# P01_Power_Management.net
KiCad netlist of a schematic drawn in Altium Designer
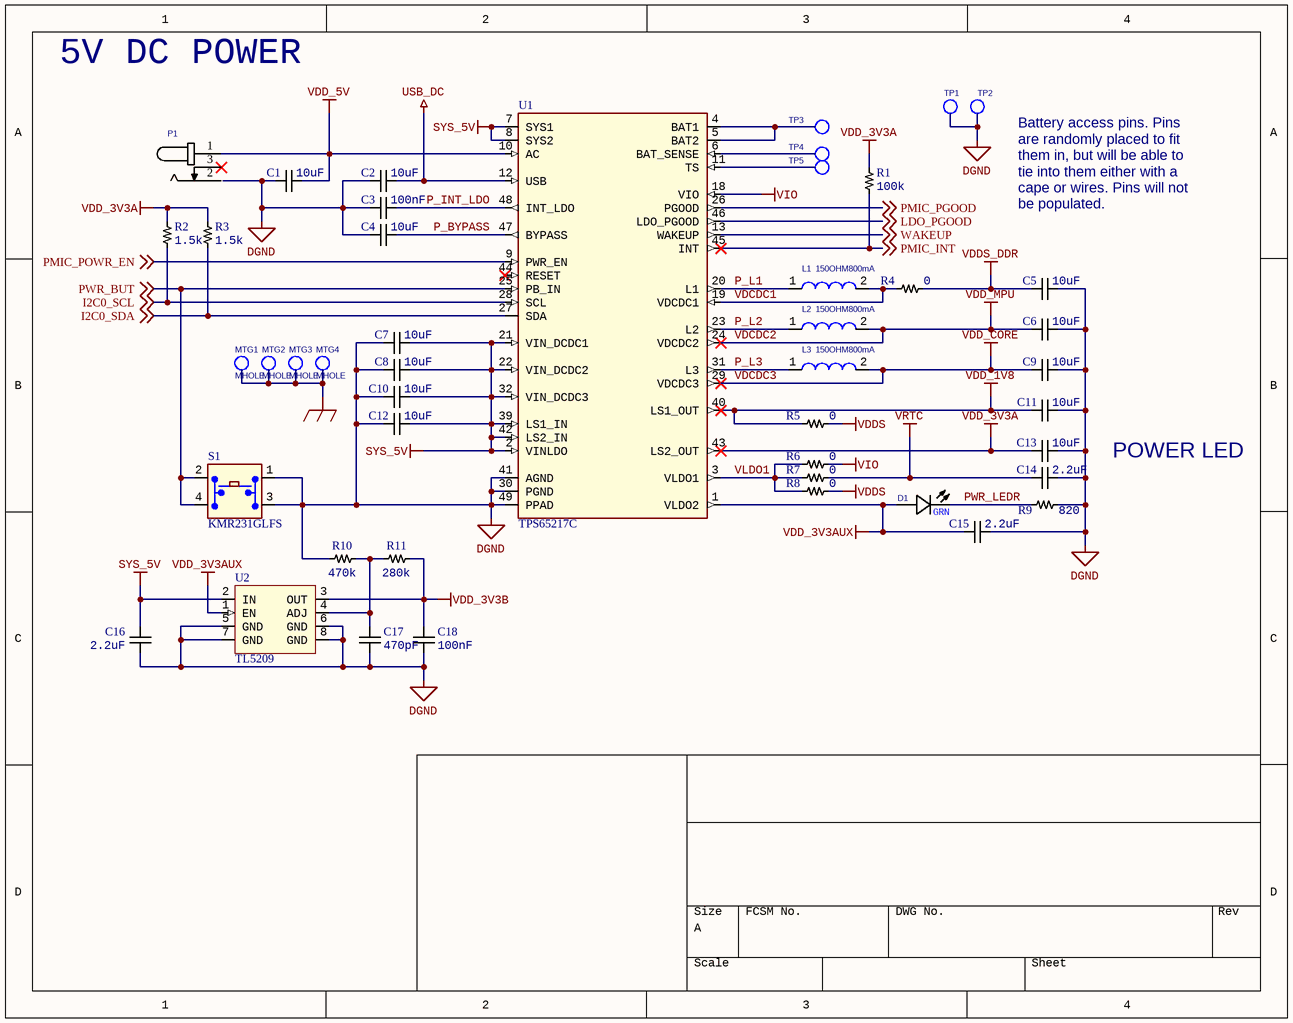
[diagram p0: P01_Power Management.SchDoc]

(export (version "E")
  (design (tool "Eeschema 10.0.6"))
  (components
    (comp (ref "C1")
      (value "C2012X6S1A106K085AC")
      (footprint "CAP0805")
      (description "MLCC 10uF 0805 SMD")
      (fields
        (field (name "MANUFACTURER") "TDK")
        (field (name "TOLERANCE") "10%")
        (field (name "CAPACITANCE") "10uF")
      )
      (libsource (lib "Orient2") (part "CAP_10uF"))
    )
    (comp (ref "C2")
      (value "C2012X6S1A106K085AC")
      (footprint "CAP0805")
      (description "MLCC 10uF 0805 SMD")
      (fields
        (field (name "MANUFACTURER") "TDK")
        (field (name "TOLERANCE") "10%")
        (field (name "CAPACITANCE") "10uF")
      )
      (libsource (lib "Orient2") (part "CAP_10uF"))
    )
    (comp (ref "C3")
      (value "C0402C104K4RACTU")
      (footprint "CAP0402")
      (description "MLCC 100nF 0402 SMD")
      (fields
        (field (name "MANUFACTURER") "KEMET")
        (field (name "TOLERANCE") "10%")
        (field (name "CAPACITANCE") "100nF")
      )
      (libsource (lib "Orient2") (part "CAP_100nF"))
    )
    (comp (ref "C4")
      (value "C2012X6S1A106K085AC")
      (footprint "CAP0805")
      (description "MLCC 10uF 0805 SMD")
      (fields
        (field (name "MANUFACTURER") "TDK")
        (field (name "TOLERANCE") "10%")
        (field (name "CAPACITANCE") "10uF")
      )
      (libsource (lib "Orient2") (part "CAP_10uF"))
    )
    (comp (ref "C5")
      (value "C2012X6S1A106K085AC")
      (footprint "CAP0805")
      (description "MLCC 10uF 0805 SMD")
      (fields
        (field (name "MANUFACTURER") "TDK")
        (field (name "TOLERANCE") "10%")
        (field (name "CAPACITANCE") "10uF")
      )
      (libsource (lib "Orient2") (part "CAP_10uF"))
    )
    (comp (ref "C6")
      (value "C2012X6S1A106K085AC")
      (footprint "CAP0805")
      (description "MLCC 10uF 0805 SMD")
      (fields
        (field (name "MANUFACTURER") "TDK")
        (field (name "TOLERANCE") "10%")
        (field (name "CAPACITANCE") "10uF")
      )
      (libsource (lib "Orient2") (part "CAP_10uF"))
    )
    (comp (ref "C7")
      (value "C2012X6S1A106K085AC")
      (footprint "CAP0805")
      (description "MLCC 10uF 0805 SMD")
      (fields
        (field (name "MANUFACTURER") "TDK")
        (field (name "TOLERANCE") "10%")
        (field (name "CAPACITANCE") "10uF")
      )
      (libsource (lib "Orient2") (part "CAP_10uF"))
    )
    (comp (ref "C8")
      (value "C2012X6S1A106K085AC")
      (footprint "CAP0805")
      (description "MLCC 10uF 0805 SMD")
      (fields
        (field (name "MANUFACTURER") "TDK")
        (field (name "TOLERANCE") "10%")
        (field (name "CAPACITANCE") "10uF")
      )
      (libsource (lib "Orient2") (part "CAP_10uF"))
    )
    (comp (ref "C9")
      (value "C2012X6S1A106K085AC")
      (footprint "CAP0805")
      (description "MLCC 10uF 0805 SMD")
      (fields
        (field (name "MANUFACTURER") "TDK")
        (field (name "TOLERANCE") "10%")
        (field (name "CAPACITANCE") "10uF")
      )
      (libsource (lib "Orient2") (part "CAP_10uF"))
    )
    (comp (ref "C10")
      (value "C2012X6S1A106K085AC")
      (footprint "CAP0805")
      (description "MLCC 10uF 0805 SMD")
      (fields
        (field (name "MANUFACTURER") "TDK")
        (field (name "TOLERANCE") "10%")
        (field (name "CAPACITANCE") "10uF")
      )
      (libsource (lib "Orient2") (part "CAP_10uF"))
    )
    (comp (ref "C11")
      (value "C2012X6S1A106K085AC")
      (footprint "CAP0805")
      (description "MLCC 10uF 0805 SMD")
      (fields
        (field (name "MANUFACTURER") "TDK")
        (field (name "TOLERANCE") "10%")
        (field (name "CAPACITANCE") "10uF")
      )
      (libsource (lib "Orient2") (part "CAP_10uF"))
    )
    (comp (ref "C12")
      (value "C2012X6S1A106K085AC")
      (footprint "CAP0805")
      (description "MLCC 10uF 0805 SMD")
      (fields
        (field (name "MANUFACTURER") "TDK")
        (field (name "TOLERANCE") "10%")
        (field (name "CAPACITANCE") "10uF")
      )
      (libsource (lib "Orient2") (part "CAP_10uF"))
    )
    (comp (ref "C13")
      (value "C2012X6S1A106K085AC")
      (footprint "CAP0805")
      (description "MLCC 10uF 0805 SMD")
      (fields
        (field (name "MANUFACTURER") "TDK")
        (field (name "TOLERANCE") "10%")
        (field (name "CAPACITANCE") "10uF")
      )
      (libsource (lib "Orient2") (part "CAP_10uF"))
    )
    (comp (ref "C14")
      (value "C1005X5R0J225K050BC")
      (footprint "CAP0402")
      (description "MLCC 2.2uF 0402 SMD")
      (fields
        (field (name "MANUFACTURER") "TDK")
        (field (name "TOLERANCE") "10%")
        (field (name "CAPACITANCE") "2.2uF")
      )
      (libsource (lib "Orient2") (part "CAP_2.2uF"))
    )
    (comp (ref "C15")
      (value "C1005X5R0J225K050BC")
      (footprint "CAP0402")
      (description "MLCC 2.2uF 0402 SMD")
      (fields
        (field (name "MANUFACTURER") "TDK")
        (field (name "TOLERANCE") "10%")
        (field (name "CAPACITANCE") "2.2uF")
      )
      (libsource (lib "Orient2") (part "CAP_2.2uF"))
    )
    (comp (ref "C16")
      (value "C1005X5R0J225K050BC")
      (footprint "CAP0402")
      (description "MLCC 2.2uF 0402 SMD")
      (fields
        (field (name "MANUFACTURER") "TDK")
        (field (name "TOLERANCE") "10%")
        (field (name "CAPACITANCE") "2.2uF")
      )
      (libsource (lib "Orient2") (part "CAP_2.2uF"))
    )
    (comp (ref "C17")
      (value "GRM155R71H471KA01D")
      (footprint "CAP0402")
      (description "MLCC 470pF 0402 SMD")
      (fields
        (field (name "MANUFACTURER") "Murata")
        (field (name "TOLERANCE") "10%")
        (field (name "CAPACITANCE") "470pF")
      )
      (libsource (lib "Orient2") (part "CAP_470pF"))
    )
    (comp (ref "C18")
      (value "C0402C104K4RACTU")
      (footprint "CAP0402")
      (description "MLCC 100nF 0402 SMD")
      (fields
        (field (name "MANUFACTURER") "KEMET")
        (field (name "TOLERANCE") "10%")
        (field (name "CAPACITANCE") "100nF")
      )
      (libsource (lib "Orient2") (part "CAP_100nF"))
    )
    (comp (ref "D1")
      (value "598-8170-107F")
      (footprint "LED_0603")
      (description "LED GREEN CLEAR 0805 SMD")
      (fields
        (field (name "MANUFACTURER") "Lite-On Inc")
        (field (name "MANUFACTURER PART NUMBER") "LTST-C170KGKT")
      )
      (libsource (lib "Orient2") (part "LED_LTST-C150GKT"))
    )
    (comp (ref "L1")
      (value "150OHM800mA")
      (footprint "FB0805")
      (description "FERRITE 800MA 150 OHM 0805 SMD")
      (fields
        (field (name "MANUFACTURER") "Laird-Signal Integrity Products")
        (field (name "MANUFACTURER PART NUMBER") "LI0805H151R-10")
      )
      (libsource (lib "Orient2") (part "IND"))
    )
    (comp (ref "L2")
      (value "150OHM800mA")
      (footprint "FB0805")
      (description "FERRITE 800MA 150 OHM 0805 SMD")
      (fields
        (field (name "MANUFACTURER") "Laird-Signal Integrity Products")
        (field (name "MANUFACTURER PART NUMBER") "LI0805H151R-10")
      )
      (libsource (lib "Orient2") (part "IND"))
    )
    (comp (ref "L3")
      (value "150OHM800mA")
      (footprint "FB0805")
      (description "FERRITE 800MA 150 OHM 0805 SMD")
      (fields
        (field (name "MANUFACTURER") "Laird-Signal Integrity Products")
        (field (name "MANUFACTURER PART NUMBER") "LI0805H151R-10")
      )
      (libsource (lib "Orient2") (part "IND"))
    )
    (comp (ref "MTG1")
      (value "MHOLE")
      (footprint "MTGH200C125D_PL")
      (libsource (lib "Orient2") (part "MHOLE"))
    )
    (comp (ref "MTG2")
      (value "MHOLE")
      (footprint "MTGH200C125D_PL")
      (libsource (lib "Orient2") (part "MHOLE"))
    )
    (comp (ref "MTG3")
      (value "MHOLE")
      (footprint "MTGH200C125D_PL")
      (libsource (lib "Orient2") (part "MHOLE"))
    )
    (comp (ref "MTG4")
      (value "MHOLE")
      (footprint "MTGH200C125D_PL")
      (libsource (lib "Orient2") (part "MHOLE"))
    )
    (comp (ref "P1")
      (value "PJ-200A")
      (description "CONN PWR JACK 2.1X5.5MM HIGH CUR")
      (fields (field (name "MANUFACTURER") "CUI Inc") (field (name "MANUFACTURER PART NUMBER") "PJ-002AH"))
      (libsource (lib "Orient2") (part "Power_Jack"))
    )
    (comp (ref "R1")
      (value "RC0402FR-07100KL")
      (footprint "RES0402")
      (description "Resistor 100kOhm 0402 SMD")
      (fields
        (field (name "MANUFACTURER") "Yageo")
        (field (name "TOLERANCE") "1%")
        (field (name "RESISTANCE") "100k")
      )
      (libsource (lib "Orient2") (part "RES_100k"))
    )
    (comp (ref "R2")
      (value "RC0402FR-071K5L")
      (footprint "RES0402")
      (description "Resistor 1.5kOhm 0402 SMD")
      (fields
        (field (name "MANUFACTURER") "Yageo")
        (field (name "TOLERANCE") "1%")
        (field (name "RESISTANCE") "1.5k")
      )
      (libsource (lib "Orient2") (part "RES_1.5k"))
    )
    (comp (ref "R3")
      (value "RC0402FR-071K5L")
      (footprint "RES0402")
      (description "Resistor 1.5kOhm 0402 SMD")
      (fields
        (field (name "MANUFACTURER") "Yageo")
        (field (name "TOLERANCE") "1%")
        (field (name "RESISTANCE") "1.5k")
      )
      (libsource (lib "Orient2") (part "RES_1.5k"))
    )
    (comp (ref "R4")
      (value "RC0402JR-070RL")
      (footprint "RES0402")
      (description "Resistor 0Ohm 0402 SMD")
      (fields
        (field (name "MANUFACTURER") "Yageo")
        (field (name "TOLERANCE") "5%")
        (field (name "RESISTANCE") "0")
      )
      (libsource (lib "Orient2") (part "RES_0"))
    )
    (comp (ref "R5")
      (value "RC0402JR-070RL")
      (footprint "RES0402")
      (description "Resistor 0Ohm 0402 SMD")
      (fields
        (field (name "MANUFACTURER") "Yageo")
        (field (name "TOLERANCE") "5%")
        (field (name "RESISTANCE") "0")
      )
      (libsource (lib "Orient2") (part "RES_0"))
    )
    (comp (ref "R6")
      (value "RC0402JR-070RL")
      (footprint "RES0402")
      (description "Resistor 0Ohm 0402 SMD")
      (fields
        (field (name "MANUFACTURER") "Yageo")
        (field (name "TOLERANCE") "5%")
        (field (name "RESISTANCE") "0")
      )
      (libsource (lib "Orient2") (part "RES_0"))
    )
    (comp (ref "R7")
      (value "RC0402JR-070RL")
      (footprint "RES0402")
      (description "Resistor 0Ohm 0402 SMD")
      (fields
        (field (name "MANUFACTURER") "Yageo")
        (field (name "TOLERANCE") "5%")
        (field (name "RESISTANCE") "0")
      )
      (libsource (lib "Orient2") (part "RES_0"))
    )
    (comp (ref "R8")
      (value "RC0402JR-070RL")
      (footprint "RES0402")
      (description "Resistor 0Ohm 0402 SMD")
      (fields
        (field (name "MANUFACTURER") "Yageo")
        (field (name "TOLERANCE") "5%")
        (field (name "RESISTANCE") "0")
      )
      (libsource (lib "Orient2") (part "RES_0"))
    )
    (comp (ref "R9")
      (value "RC0402FR-07820RL")
      (footprint "RES0402")
      (description "Resistor 820Ohm 0402 SMD")
      (fields
        (field (name "MANUFACTURER") "Yageo")
        (field (name "TOLERANCE") "1%")
        (field (name "RESISTANCE") "820")
      )
      (libsource (lib "Orient2") (part "RES_820"))
    )
    (comp (ref "R10")
      (value "RC0402FR-07470KL")
      (footprint "RES0402")
      (description "Resistor 470kOhm 0402 SMD")
      (fields
        (field (name "MANUFACTURER") "Yageo")
        (field (name "TOLERANCE") "1%")
        (field (name "RESISTANCE") "470k")
      )
      (libsource (lib "Orient2") (part "RES_470k"))
    )
    (comp (ref "R11")
      (value "RC0402FR-07280KL")
      (footprint "RES0402")
      (description "Resistor 280kOhm 0402 SMD")
      (fields
        (field (name "MANUFACTURER") "Yageo")
        (field (name "TOLERANCE") "1%")
        (field (name "RESISTANCE") "280k")
      )
      (libsource (lib "Orient2") (part "RES_280k"))
    )
    (comp (ref "S1")
      (value "KMR231GLFS")
      (footprint "SW4SMD_63X161LS")
      (description "Microminiature Tact Switch for SMT")
      (fields (field (name "MANUFACTURER") "C&K Components"))
      (libsource (lib "Orient2") (part "KMR2"))
    )
    (comp (ref "TP1") (value "TESTPT1") (footprint "tp1-8040") (libsource (lib "Orient2") (part "TESTPT1")))
    (comp (ref "TP2") (value "TESTPT1") (footprint "tp1-8040") (libsource (lib "Orient2") (part "TESTPT1")))
    (comp (ref "TP3") (value "TESTPT1") (footprint "tp1-8040") (libsource (lib "Orient2") (part "TESTPT1")))
    (comp (ref "TP4") (value "TESTPT1") (footprint "tp1-8040") (libsource (lib "Orient2") (part "TESTPT1")))
    (comp (ref "TP5") (value "TESTPT1") (footprint "tp1-8040") (libsource (lib "Orient2") (part "TESTPT1")))
    (comp (ref "U1")
      (value "TPS65217C")
      (footprint "PVQFN-48")
      (description "IC PMIC BATT PWR SYST 48VQFN")
      (fields
        (field (name "MANUFACTURER") "Texas Instruments")
        (field (name "MANUFACTURER PART NUMBER") "TPS65217CRSLR")
      )
      (libsource (lib "Orient2") (part "TPS65217C"))
    )
    (comp (ref "U2")
      (value "TL5209")
      (footprint "SOIC-8")
      (description "LDO Voltage Regulator")
      (fields
        (field (name "MANUFACTURER") "Texas Instruments")
        (field (name "MANUFACTURER PART NUMBER") "TL5209DR")
      )
      (libsource (lib "Orient2") (part "TL5209"))
    )
  )
  (nets
    (net (code "1") (name "/PWR_LEDR") (class "Default")
      (node (ref "D1") (pin "1") (pinfunction "C_1") (pintype "passive"))
      (node (ref "R9") (pin "1") (pintype "passive"))
    )
    (net (code "2") (name "/P_BYPASS") (class "Default")
      (node (ref "C4") (pin "1") (pintype "passive"))
      (node (ref "U1") (pin "47") (pinfunction "BYPASS_47") (pintype "output"))
    )
    (net (code "3") (name "/P_INT_LDO") (class "Default")
      (node (ref "C3") (pin "1") (pintype "passive"))
      (node (ref "U1") (pin "48") (pinfunction "INT_LDO_48") (pintype "output"))
    )
    (net (code "4") (name "/P_L1") (class "Default")
      (node (ref "L1") (pin "1") (pinfunction "1_1") (pintype "passive"))
      (node (ref "U1") (pin "20") (pinfunction "L1_20") (pintype "output"))
    )
    (net (code "5") (name "/P_L2") (class "Default")
      (node (ref "L2") (pin "1") (pinfunction "1_1") (pintype "passive"))
      (node (ref "U1") (pin "23") (pinfunction "L2_23") (pintype "output"))
    )
    (net (code "6") (name "/P_L3") (class "Default")
      (node (ref "L3") (pin "1") (pinfunction "1_1") (pintype "passive"))
      (node (ref "U1") (pin "31") (pinfunction "L3_31") (pintype "output"))
    )
    (net (code "7") (name "/VDCDC1") (class "Default")
      (node (ref "L1") (pin "2") (pinfunction "2_2") (pintype "passive"))
      (node (ref "R4") (pin "1") (pintype "passive"))
      (node (ref "U1") (pin "19") (pinfunction "VDCDC1_19") (pintype "input"))
    )
    (net (code "8") (name "/VLDO1") (class "Default")
      (node (ref "R6") (pin "1") (pintype "passive"))
      (node (ref "R7") (pin "1") (pintype "passive"))
      (node (ref "R8") (pin "1") (pintype "passive"))
      (node (ref "U1") (pin "3") (pinfunction "VLDO1_3") (pintype "output"))
    )
    (net (code "9") (name "DGND") (class "Default")
      (node (ref "C1") (pin "2") (pintype "passive"))
      (node (ref "C10") (pin "2") (pintype "passive"))
      (node (ref "C11") (pin "1") (pintype "passive"))
      (node (ref "C12") (pin "2") (pintype "passive"))
      (node (ref "C13") (pin "1") (pintype "passive"))
      (node (ref "C14") (pin "1") (pintype "passive"))
      (node (ref "C15") (pin "1") (pintype "passive"))
      (node (ref "C16") (pin "2") (pintype "passive"))
      (node (ref "C17") (pin "2") (pintype "passive"))
      (node (ref "C18") (pin "2") (pintype "passive"))
      (node (ref "C2") (pin "2") (pintype "passive"))
      (node (ref "C3") (pin "2") (pintype "passive"))
      (node (ref "C4") (pin "2") (pintype "passive"))
      (node (ref "C5") (pin "1") (pintype "passive"))
      (node (ref "C6") (pin "1") (pintype "passive"))
      (node (ref "C7") (pin "2") (pintype "passive"))
      (node (ref "C8") (pin "2") (pintype "passive"))
      (node (ref "C9") (pin "1") (pintype "passive"))
      (node (ref "R10") (pin "1") (pintype "passive"))
      (node (ref "R9") (pin "2") (pintype "passive"))
      (node (ref "S1") (pin "1") (pinfunction "A1_1") (pintype "passive"))
      (node (ref "S1") (pin "3") (pinfunction "A3_3") (pintype "passive"))
      (node (ref "TP1") (pin "1") (pinfunction "TP_1") (pintype "passive"))
      (node (ref "TP2") (pin "1") (pinfunction "TP_1") (pintype "passive"))
      (node (ref "U1") (pin "30") (pinfunction "PGND_30") (pintype "power_in"))
      (node (ref "U1") (pin "41") (pinfunction "AGND_41") (pintype "power_in"))
      (node (ref "U1") (pin "49") (pinfunction "PPAD_49") (pintype "power_in"))
      (node (ref "U2") (pin "5") (pinfunction "GND_5") (pintype "power_in"))
      (node (ref "U2") (pin "6") (pinfunction "GND_6") (pintype "power_in"))
      (node (ref "U2") (pin "7") (pinfunction "GND_7") (pintype "power_in"))
      (node (ref "U2") (pin "8") (pinfunction "GND_8") (pintype "power_in"))
    )
    (net (code "10") (name "GND_EARTH") (class "Default")
      (node (ref "MTG1") (pin "1") (pinfunction "TP_1") (pintype "passive"))
      (node (ref "MTG2") (pin "1") (pinfunction "TP_1") (pintype "passive"))
      (node (ref "MTG3") (pin "1") (pinfunction "TP_1") (pintype "passive"))
      (node (ref "MTG4") (pin "1") (pinfunction "TP_1") (pintype "passive"))
    )
    (net (code "11") (name "I2C0_SCL") (class "Default")
      (node (ref "R2") (pin "1") (pintype "passive"))
      (node (ref "U1") (pin "28") (pinfunction "SCL_28") (pintype "input"))
    )
    (net (code "12") (name "I2C0_SDA") (class "Default")
      (node (ref "R3") (pin "1") (pintype "passive"))
      (node (ref "U1") (pin "27") (pinfunction "SDA_27") (pintype "bidirectional"))
    )
    (net (code "13") (name "LDO_PGOOD") (class "Default")
      (node (ref "U1") (pin "46") (pinfunction "LDO_PGOOD_46") (pintype "output"))
    )
    (net (code "14") (name "Net-(TP3-TP)") (class "Default")
      (node (ref "TP3") (pin "1") (pinfunction "TP_1") (pintype "passive"))
      (node (ref "U1") (pin "4") (pinfunction "BAT1_4") (pintype "bidirectional"))
      (node (ref "U1") (pin "5") (pinfunction "BAT2_5") (pintype "bidirectional"))
    )
    (net (code "15") (name "Net-(TP4-TP)") (class "Default")
      (node (ref "TP4") (pin "1") (pinfunction "TP_1") (pintype "passive"))
      (node (ref "U1") (pin "6") (pinfunction "BAT_SENSE_6") (pintype "input"))
    )
    (net (code "16") (name "Net-(TP5-TP)") (class "Default")
      (node (ref "TP5") (pin "1") (pinfunction "TP_1") (pintype "passive"))
      (node (ref "U1") (pin "11") (pinfunction "TS_11") (pintype "input"))
    )
    (net (code "17") (name "Net-(U2-ADJ)") (class "Default")
      (node (ref "C17") (pin "1") (pintype "passive"))
      (node (ref "R10") (pin "2") (pintype "passive"))
      (node (ref "R11") (pin "1") (pintype "passive"))
      (node (ref "U2") (pin "4") (pinfunction "ADJ_4") (pintype "passive"))
    )
    (net (code "18") (name "PMIC_INT") (class "Default")
      (node (ref "R1") (pin "1") (pintype "passive"))
      (node (ref "U1") (pin "45") (pinfunction "INT_45") (pintype "output"))
    )
    (net (code "19") (name "PMIC_PGOOD") (class "Default")
      (node (ref "U1") (pin "26") (pinfunction "PGOOD_26") (pintype "output"))
    )
    (net (code "20") (name "PMIC_POWR_EN") (class "Default")
      (node (ref "U1") (pin "9") (pinfunction "PWR_EN_9") (pintype "input"))
    )
    (net (code "21") (name "PWR_BUT") (class "Default")
      (node (ref "S1") (pin "2") (pinfunction "A2_2") (pintype "passive"))
      (node (ref "S1") (pin "4") (pinfunction "4_4") (pintype "power_in"))
      (node (ref "U1") (pin "25") (pinfunction "PB_IN_25") (pintype "input"))
    )
    (net (code "22") (name "SYS_5V") (class "Default")
      (node (ref "C10") (pin "1") (pintype "passive"))
      (node (ref "C12") (pin "1") (pintype "passive"))
      (node (ref "C16") (pin "1") (pintype "passive"))
      (node (ref "C7") (pin "1") (pintype "passive"))
      (node (ref "C8") (pin "1") (pintype "passive"))
      (node (ref "U1") (pin "2") (pinfunction "VINLDO_2") (pintype "input"))
      (node (ref "U1") (pin "21") (pinfunction "VIN_DCDC1_21") (pintype "input"))
      (node (ref "U1") (pin "22") (pinfunction "VIN_DCDC2_22") (pintype "input"))
      (node (ref "U1") (pin "32") (pinfunction "VIN_DCDC3_32") (pintype "input"))
      (node (ref "U1") (pin "39") (pinfunction "LS1_IN_39") (pintype "input"))
      (node (ref "U1") (pin "42") (pinfunction "LS2_IN_42") (pintype "input"))
      (node (ref "U1") (pin "7") (pinfunction "SYS1_7") (pintype "passive"))
      (node (ref "U1") (pin "8") (pinfunction "SYS2_8") (pintype "passive"))
      (node (ref "U2") (pin "2") (pinfunction "IN_2") (pintype "power_in"))
    )
    (net (code "23") (name "USB_DC") (class "Default")
      (node (ref "C2") (pin "1") (pintype "passive"))
      (node (ref "U1") (pin "12") (pinfunction "USB_12") (pintype "input"))
    )
    (net (code "24") (name "VDDS") (class "Default")
      (node (ref "R5") (pin "2") (pintype "passive"))
      (node (ref "R8") (pin "2") (pintype "passive"))
    )
    (net (code "25") (name "VDDS_DDR") (class "Default")
      (node (ref "C5") (pin "2") (pintype "passive"))
      (node (ref "R4") (pin "2") (pintype "passive"))
    )
    (net (code "26") (name "VDD_1V8") (class "Default")
      (node (ref "C11") (pin "2") (pintype "passive"))
      (node (ref "R5") (pin "1") (pintype "passive"))
      (node (ref "U1") (pin "40") (pinfunction "LS1_OUT_40") (pintype "output"))
    )
    (net (code "27") (name "VDD_3V3A") (class "Default")
      (node (ref "C13") (pin "2") (pintype "passive"))
      (node (ref "R1") (pin "2") (pintype "passive"))
      (node (ref "R2") (pin "2") (pintype "passive"))
      (node (ref "R3") (pin "2") (pintype "passive"))
      (node (ref "U1") (pin "43") (pinfunction "LS2_OUT_43") (pintype "output"))
    )
    (net (code "28") (name "VDD_3V3AUX") (class "Default")
      (node (ref "C15") (pin "2") (pintype "passive"))
      (node (ref "D1") (pin "2") (pinfunction "A_2") (pintype "passive"))
      (node (ref "U1") (pin "1") (pinfunction "VLDO2_1") (pintype "output"))
      (node (ref "U2") (pin "1") (pinfunction "EN_1") (pintype "input"))
    )
    (net (code "29") (name "VDD_3V3B") (class "Default")
      (node (ref "C18") (pin "1") (pintype "passive"))
      (node (ref "R11") (pin "2") (pintype "passive"))
      (node (ref "U2") (pin "3") (pinfunction "OUT_3") (pintype "power_in"))
    )
    (net (code "30") (name "VDD_5V") (class "Default")
      (node (ref "C1") (pin "1") (pintype "passive"))
      (node (ref "P1") (pin "1") (pinfunction "1_1") (pintype "passive"))
      (node (ref "U1") (pin "10") (pinfunction "AC_10") (pintype "input"))
    )
    (net (code "31") (name "VDD_CORE") (class "Default")
      (node (ref "C9") (pin "2") (pintype "passive"))
      (node (ref "L3") (pin "2") (pinfunction "2_2") (pintype "passive"))
      (node (ref "U1") (pin "29") (pinfunction "VDCDC3_29") (pintype "output"))
    )
    (net (code "32") (name "VDD_MPU") (class "Default")
      (node (ref "C6") (pin "2") (pintype "passive"))
      (node (ref "L2") (pin "2") (pinfunction "2_2") (pintype "passive"))
      (node (ref "U1") (pin "24") (pinfunction "VDCDC2_24") (pintype "output"))
    )
    (net (code "33") (name "VIO") (class "Default")
      (node (ref "R6") (pin "2") (pintype "passive"))
      (node (ref "U1") (pin "18") (pinfunction "VIO_18") (pintype "input"))
    )
    (net (code "34") (name "VRTC") (class "Default")
      (node (ref "C14") (pin "2") (pintype "passive"))
      (node (ref "R7") (pin "2") (pintype "passive"))
    )
    (net (code "35") (name "WAKEUP") (class "Default")
      (node (ref "U1") (pin "13") (pinfunction "WAKEUP_13") (pintype "output"))
    )
    (net (code "36") (name "unconnected-(P1-Pad2)") (class "Default")
      (node (ref "P1") (pin "2") (pinfunction "2_2") (pintype "passive"))
    )
    (net (code "37") (name "unconnected-(P1-Pad3)") (class "Default")
      (node (ref "P1") (pin "3") (pinfunction "3_3") (pintype "passive+no_connect"))
    )
    (net (code "38") (name "unconnected-(U1-RESET-Pad44)") (class "Default")
      (node (ref "U1") (pin "44") (pinfunction "RESET_44") (pintype "input+no_connect"))
    )
  )
)
